# Lampen.net
KiCad netlist of a schematic drawn in EAGLE
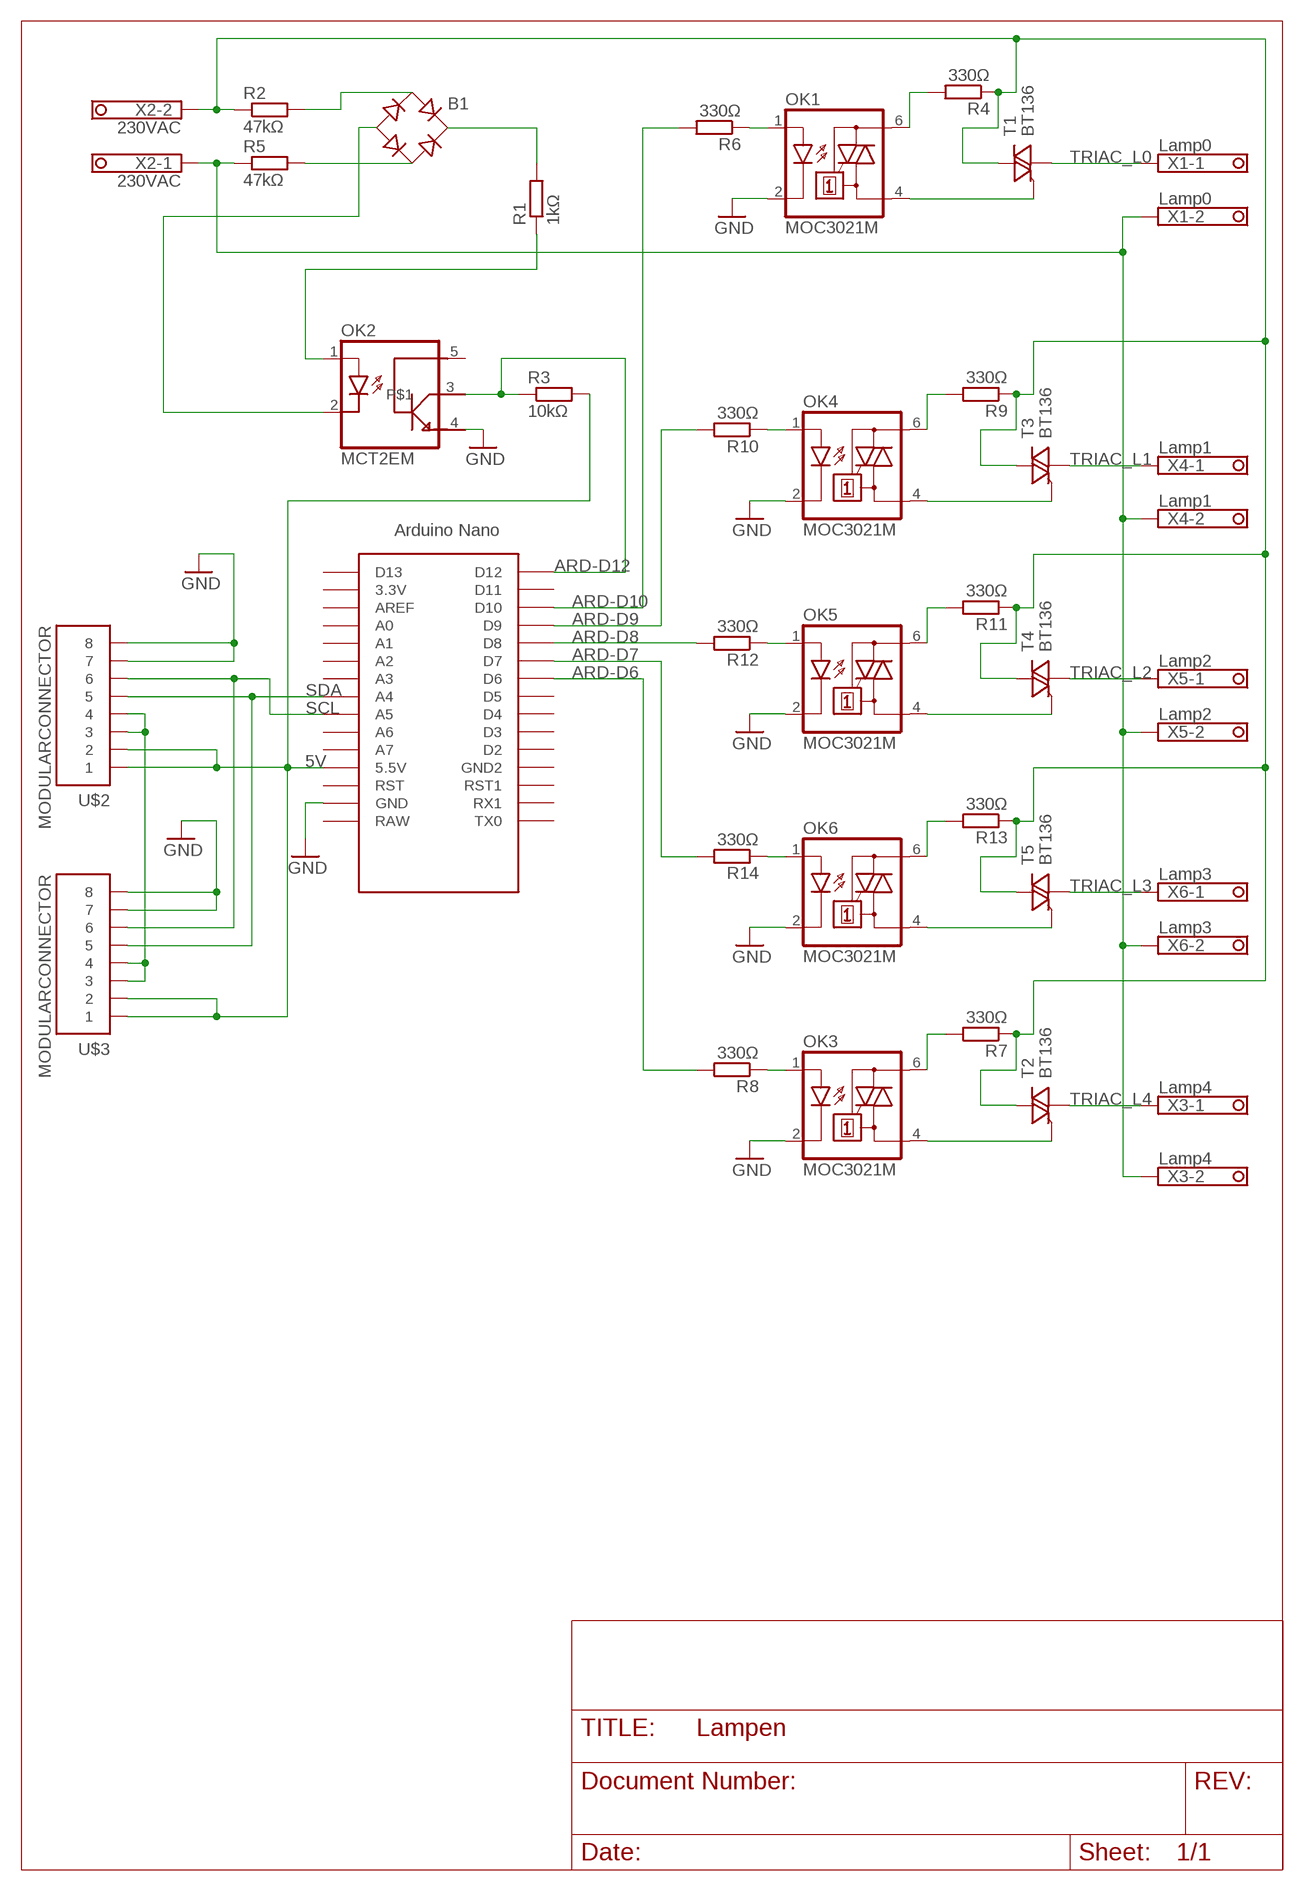
[diagram p0: schematic, sheet 1]

(export (version "E")
  (design (tool "Eeschema 10.0.6"))
  (components
    (comp (ref "B1")
      (value "B250C1500G")
      (footprint "eagle-import:RB1A")
      (libsource (lib "eagle-import") (part "B250C1500G"))
    )
    (comp (ref "OK1")
      (value "MOC3021M")
      (footprint "eagle-import:DIL06")
      (fields (field (name "MF") "FAIRCHILD SEMICONDUCTOR") (field (name "MPN") "MOC3010-M"))
      (libsource (lib "eagle-import") (part "MOC3021M10"))
    )
    (comp (ref "OK2")
      (value "MCT2EM")
      (footprint "eagle-import:DIL06")
      (fields (field (name "MF") "FAIRCHILD SEMICONDUCTOR") (field (name "MPN") "MOC3021-M"))
      (libsource (lib "eagle-import") (part "MCT2EM21"))
    )
    (comp (ref "OK3")
      (value "MOC3021M")
      (footprint "eagle-import:DIL06")
      (fields (field (name "MF") "FAIRCHILD SEMICONDUCTOR") (field (name "MPN") "MOC3010-M"))
      (libsource (lib "eagle-import") (part "MOC3021M10"))
    )
    (comp (ref "OK4")
      (value "MOC3021M")
      (footprint "eagle-import:DIL06")
      (fields (field (name "MF") "FAIRCHILD SEMICONDUCTOR") (field (name "MPN") "MOC3010-M"))
      (libsource (lib "eagle-import") (part "MOC3021M10"))
    )
    (comp (ref "OK5")
      (value "MOC3021M")
      (footprint "eagle-import:DIL06")
      (fields (field (name "MF") "FAIRCHILD SEMICONDUCTOR") (field (name "MPN") "MOC3010-M"))
      (libsource (lib "eagle-import") (part "MOC3021M10"))
    )
    (comp (ref "OK6")
      (value "MOC3021M")
      (footprint "eagle-import:DIL06")
      (fields (field (name "MF") "FAIRCHILD SEMICONDUCTOR") (field (name "MPN") "MOC3010-M"))
      (libsource (lib "eagle-import") (part "MOC3021M10"))
    )
    (comp (ref "R1")
      (value "1kΩ")
      (footprint "eagle-import:M1206")
      (libsource (lib "eagle-import") (part "R-EU_M1206"))
    )
    (comp (ref "R2")
      (value "47kΩ")
      (footprint "eagle-import:R2512")
      (libsource (lib "eagle-import") (part "R-EU_R2512"))
    )
    (comp (ref "R3")
      (value "10kΩ")
      (footprint "eagle-import:M1206")
      (libsource (lib "eagle-import") (part "R-EU_M1206"))
    )
    (comp (ref "R4")
      (value "330Ω")
      (footprint "eagle-import:M1206")
      (libsource (lib "eagle-import") (part "R-EU_M1206"))
    )
    (comp (ref "R5")
      (value "47kΩ")
      (footprint "eagle-import:R2512")
      (libsource (lib "eagle-import") (part "R-EU_R2512"))
    )
    (comp (ref "R6")
      (value "330Ω")
      (footprint "eagle-import:M1206")
      (libsource (lib "eagle-import") (part "R-EU_M1206"))
    )
    (comp (ref "R7")
      (value "330Ω")
      (footprint "eagle-import:M1206")
      (libsource (lib "eagle-import") (part "R-EU_M1206"))
    )
    (comp (ref "R8")
      (value "330Ω")
      (footprint "eagle-import:M1206")
      (libsource (lib "eagle-import") (part "R-EU_M1206"))
    )
    (comp (ref "R9")
      (value "330Ω")
      (footprint "eagle-import:M1206")
      (libsource (lib "eagle-import") (part "R-EU_M1206"))
    )
    (comp (ref "R10")
      (value "330Ω")
      (footprint "eagle-import:M1206")
      (libsource (lib "eagle-import") (part "R-EU_M1206"))
    )
    (comp (ref "R11")
      (value "330Ω")
      (footprint "eagle-import:M1206")
      (libsource (lib "eagle-import") (part "R-EU_M1206"))
    )
    (comp (ref "R12")
      (value "330Ω")
      (footprint "eagle-import:M1206")
      (libsource (lib "eagle-import") (part "R-EU_M1206"))
    )
    (comp (ref "R13")
      (value "330Ω")
      (footprint "eagle-import:M1206")
      (libsource (lib "eagle-import") (part "R-EU_M1206"))
    )
    (comp (ref "R14")
      (value "330Ω")
      (footprint "eagle-import:M1206")
      (libsource (lib "eagle-import") (part "R-EU_M1206"))
    )
    (comp (ref "T1")
      (value "BT136")
      (footprint "eagle-import:TO220DS")
      (libsource (lib "eagle-import") (part "BT136"))
    )
    (comp (ref "T2")
      (value "BT136")
      (footprint "eagle-import:TO220DS")
      (libsource (lib "eagle-import") (part "BT136"))
    )
    (comp (ref "T3")
      (value "BT136")
      (footprint "eagle-import:TO220DS")
      (libsource (lib "eagle-import") (part "BT136"))
    )
    (comp (ref "T4")
      (value "BT136")
      (footprint "eagle-import:TO220DS")
      (libsource (lib "eagle-import") (part "BT136"))
    )
    (comp (ref "T5")
      (value "BT136")
      (footprint "eagle-import:TO220DS")
      (libsource (lib "eagle-import") (part "BT136"))
    )
    (comp (ref "U$1")
      (value "NANO")
      (footprint "eagle-import:NANO")
      (libsource (lib "eagle-import") (part "NANO"))
    )
    (comp (ref "U$2")
      (value "MODULARCONNECTOR")
      (footprint "eagle-import:MA04-2")
      (libsource (lib "eagle-import") (part "MODULARCONNECTOR"))
    )
    (comp (ref "U$3")
      (value "MODULARCONNECTOR")
      (footprint "eagle-import:MA04-2")
      (libsource (lib "eagle-import") (part "MODULARCONNECTOR"))
    )
    (comp (ref "X1")
      (value "Lamp0")
      (footprint "eagle-import:1751248")
      (libsource (lib "eagle-import") (part "1751248"))
    )
    (comp (ref "X2")
      (value "230VAC")
      (footprint "eagle-import:1751248")
      (libsource (lib "eagle-import") (part "1751248"))
    )
    (comp (ref "X3")
      (value "Lamp4")
      (footprint "eagle-import:1751248")
      (libsource (lib "eagle-import") (part "1751248"))
    )
    (comp (ref "X4")
      (value "Lamp1")
      (footprint "eagle-import:1751248")
      (libsource (lib "eagle-import") (part "1751248"))
    )
    (comp (ref "X5")
      (value "Lamp2")
      (footprint "eagle-import:1751248")
      (libsource (lib "eagle-import") (part "1751248"))
    )
    (comp (ref "X6")
      (value "Lamp3")
      (footprint "eagle-import:1751248")
      (libsource (lib "eagle-import") (part "1751248"))
    )
  )
  (nets
    (net (code "1") (name "/5V") (class "Default")
      (node (ref "R3") (pin "2") (pinfunction "2_2") (pintype "passive"))
      (node (ref "U$1") (pin "5V") (pinfunction "5.5V_5V") (pintype "bidirectional"))
      (node (ref "U$2") (pin "1") (pinfunction "1_1") (pintype "input"))
      (node (ref "U$2") (pin "2") (pinfunction "2_2") (pintype "input"))
      (node (ref "U$3") (pin "1") (pinfunction "1_1") (pintype "input"))
      (node (ref "U$3") (pin "2") (pinfunction "2_2") (pintype "input"))
    )
    (net (code "2") (name "/ARD-D6") (class "Default")
      (node (ref "R8") (pin "2") (pinfunction "2_2") (pintype "passive"))
      (node (ref "U$1") (pin "D6") (pinfunction "D6_D6") (pintype "bidirectional"))
    )
    (net (code "3") (name "/ARD-D7") (class "Default")
      (node (ref "R14") (pin "2") (pinfunction "2_2") (pintype "passive"))
      (node (ref "U$1") (pin "D7") (pinfunction "D7_D7") (pintype "bidirectional"))
    )
    (net (code "4") (name "/ARD-D8") (class "Default")
      (node (ref "R12") (pin "2") (pinfunction "2_2") (pintype "passive"))
      (node (ref "U$1") (pin "D8") (pinfunction "D8_D8") (pintype "bidirectional"))
    )
    (net (code "5") (name "/ARD-D9") (class "Default")
      (node (ref "R10") (pin "2") (pinfunction "2_2") (pintype "passive"))
      (node (ref "U$1") (pin "D9") (pinfunction "D9_D9") (pintype "bidirectional"))
    )
    (net (code "6") (name "/ARD-D10") (class "Default")
      (node (ref "R6") (pin "2") (pinfunction "2_2") (pintype "passive"))
      (node (ref "U$1") (pin "D10") (pinfunction "D10_D10") (pintype "bidirectional"))
    )
    (net (code "7") (name "/ARD-D12") (class "Default")
      (node (ref "OK2") (pin "3") (pinfunction "P$1_3") (pintype "bidirectional"))
      (node (ref "R3") (pin "1") (pinfunction "1_1") (pintype "passive"))
      (node (ref "U$1") (pin "D12") (pinfunction "D12_D12") (pintype "bidirectional"))
    )
    (net (code "8") (name "/SCL") (class "Default")
      (node (ref "U$1") (pin "A5") (pinfunction "A5_A5") (pintype "bidirectional"))
      (node (ref "U$2") (pin "6") (pinfunction "6_6") (pintype "input"))
      (node (ref "U$3") (pin "6") (pinfunction "6_6") (pintype "input"))
    )
    (net (code "9") (name "/SDA") (class "Default")
      (node (ref "U$1") (pin "A4") (pinfunction "A4_A4") (pintype "bidirectional"))
      (node (ref "U$2") (pin "5") (pinfunction "5_5") (pintype "input"))
      (node (ref "U$3") (pin "5") (pinfunction "5_5") (pintype "input"))
    )
    (net (code "10") (name "/TRIAC_L0") (class "Default")
      (node (ref "T1") (pin "A1") (pinfunction "A1_A1") (pintype "passive"))
      (node (ref "X1") (pin "1") (pinfunction "K_1") (pintype "passive"))
    )
    (net (code "11") (name "/TRIAC_L1") (class "Default")
      (node (ref "T3") (pin "A1") (pinfunction "A1_A1") (pintype "passive"))
      (node (ref "X4") (pin "1") (pinfunction "K_1") (pintype "passive"))
    )
    (net (code "12") (name "/TRIAC_L2") (class "Default")
      (node (ref "T4") (pin "A1") (pinfunction "A1_A1") (pintype "passive"))
      (node (ref "X5") (pin "1") (pinfunction "K_1") (pintype "passive"))
    )
    (net (code "13") (name "/TRIAC_L3") (class "Default")
      (node (ref "T5") (pin "A1") (pinfunction "A1_A1") (pintype "passive"))
      (node (ref "X6") (pin "1") (pinfunction "K_1") (pintype "passive"))
    )
    (net (code "14") (name "/TRIAC_L4") (class "Default")
      (node (ref "T2") (pin "A1") (pinfunction "A1_A1") (pintype "passive"))
      (node (ref "X3") (pin "1") (pinfunction "K_1") (pintype "passive"))
    )
    (net (code "15") (name "GND") (class "Default")
      (node (ref "OK1") (pin "2") (pinfunction "C_2") (pintype "passive"))
      (node (ref "OK2") (pin "4") (pinfunction "A1_4") (pintype "passive"))
      (node (ref "OK3") (pin "2") (pinfunction "C_2") (pintype "passive"))
      (node (ref "OK4") (pin "2") (pinfunction "C_2") (pintype "passive"))
      (node (ref "OK5") (pin "2") (pinfunction "C_2") (pintype "passive"))
      (node (ref "OK6") (pin "2") (pinfunction "C_2") (pintype "passive"))
      (node (ref "U$1") (pin "GND") (pinfunction "GND_GND") (pintype "bidirectional"))
      (node (ref "U$2") (pin "7") (pinfunction "7_7") (pintype "input"))
      (node (ref "U$2") (pin "8") (pinfunction "8_8") (pintype "input"))
      (node (ref "U$3") (pin "7") (pinfunction "7_7") (pintype "input"))
      (node (ref "U$3") (pin "8") (pinfunction "8_8") (pintype "input"))
    )
    (net (code "16") (name "Net-(B1-Pad+)") (class "Default")
      (node (ref "B1") (pin "+") (pinfunction "+_+") (pintype "passive"))
      (node (ref "R1") (pin "2") (pinfunction "2_2") (pintype "passive"))
    )
    (net (code "17") (name "Net-(B1-PadAC1)") (class "Default")
      (node (ref "B1") (pin "AC1") (pinfunction "AC1_AC1") (pintype "passive"))
      (node (ref "R2") (pin "2") (pinfunction "2_2") (pintype "passive"))
    )
    (net (code "18") (name "Net-(B1-PadAC2)") (class "Default")
      (node (ref "B1") (pin "AC2") (pinfunction "AC2_AC2") (pintype "passive"))
      (node (ref "R5") (pin "2") (pinfunction "2_2") (pintype "passive"))
    )
    (net (code "19") (name "Net-(OK1-A)") (class "Default")
      (node (ref "OK1") (pin "1") (pinfunction "A_1") (pintype "passive"))
      (node (ref "R6") (pin "1") (pinfunction "1_1") (pintype "passive"))
    )
    (net (code "20") (name "Net-(OK1-A1)") (class "Default")
      (node (ref "OK1") (pin "4") (pinfunction "A1_4") (pintype "passive"))
      (node (ref "T1") (pin "G") (pinfunction "G_G") (pintype "passive"))
    )
    (net (code "21") (name "Net-(OK1-A2)") (class "Default")
      (node (ref "OK1") (pin "6") (pinfunction "A2_6") (pintype "passive"))
      (node (ref "R4") (pin "2") (pinfunction "2_2") (pintype "passive"))
    )
    (net (code "22") (name "Net-(OK2-A)") (class "Default")
      (node (ref "OK2") (pin "1") (pinfunction "A_1") (pintype "passive"))
      (node (ref "R1") (pin "1") (pinfunction "1_1") (pintype "passive"))
    )
    (net (code "23") (name "Net-(OK2-C)") (class "Default")
      (node (ref "B1") (pin "-") (pinfunction "-_-") (pintype "passive"))
      (node (ref "OK2") (pin "2") (pinfunction "C_2") (pintype "passive"))
    )
    (net (code "24") (name "Net-(OK3-A)") (class "Default")
      (node (ref "OK3") (pin "1") (pinfunction "A_1") (pintype "passive"))
      (node (ref "R8") (pin "1") (pinfunction "1_1") (pintype "passive"))
    )
    (net (code "25") (name "Net-(OK3-A1)") (class "Default")
      (node (ref "OK3") (pin "4") (pinfunction "A1_4") (pintype "passive"))
      (node (ref "T2") (pin "G") (pinfunction "G_G") (pintype "passive"))
    )
    (net (code "26") (name "Net-(OK3-A2)") (class "Default")
      (node (ref "OK3") (pin "6") (pinfunction "A2_6") (pintype "passive"))
      (node (ref "R7") (pin "2") (pinfunction "2_2") (pintype "passive"))
    )
    (net (code "27") (name "Net-(OK4-A)") (class "Default")
      (node (ref "OK4") (pin "1") (pinfunction "A_1") (pintype "passive"))
      (node (ref "R10") (pin "1") (pinfunction "1_1") (pintype "passive"))
    )
    (net (code "28") (name "Net-(OK4-A1)") (class "Default")
      (node (ref "OK4") (pin "4") (pinfunction "A1_4") (pintype "passive"))
      (node (ref "T3") (pin "G") (pinfunction "G_G") (pintype "passive"))
    )
    (net (code "29") (name "Net-(OK4-A2)") (class "Default")
      (node (ref "OK4") (pin "6") (pinfunction "A2_6") (pintype "passive"))
      (node (ref "R9") (pin "2") (pinfunction "2_2") (pintype "passive"))
    )
    (net (code "30") (name "Net-(OK5-A)") (class "Default")
      (node (ref "OK5") (pin "1") (pinfunction "A_1") (pintype "passive"))
      (node (ref "R12") (pin "1") (pinfunction "1_1") (pintype "passive"))
    )
    (net (code "31") (name "Net-(OK5-A1)") (class "Default")
      (node (ref "OK5") (pin "4") (pinfunction "A1_4") (pintype "passive"))
      (node (ref "T4") (pin "G") (pinfunction "G_G") (pintype "passive"))
    )
    (net (code "32") (name "Net-(OK5-A2)") (class "Default")
      (node (ref "OK5") (pin "6") (pinfunction "A2_6") (pintype "passive"))
      (node (ref "R11") (pin "2") (pinfunction "2_2") (pintype "passive"))
    )
    (net (code "33") (name "Net-(OK6-A)") (class "Default")
      (node (ref "OK6") (pin "1") (pinfunction "A_1") (pintype "passive"))
      (node (ref "R14") (pin "1") (pinfunction "1_1") (pintype "passive"))
    )
    (net (code "34") (name "Net-(OK6-A1)") (class "Default")
      (node (ref "OK6") (pin "4") (pinfunction "A1_4") (pintype "passive"))
      (node (ref "T5") (pin "G") (pinfunction "G_G") (pintype "passive"))
    )
    (net (code "35") (name "Net-(OK6-A2)") (class "Default")
      (node (ref "OK6") (pin "6") (pinfunction "A2_6") (pintype "passive"))
      (node (ref "R13") (pin "2") (pinfunction "2_2") (pintype "passive"))
    )
    (net (code "36") (name "Net-(U$2-Pad3)") (class "Default")
      (node (ref "U$2") (pin "3") (pinfunction "3_3") (pintype "input"))
      (node (ref "U$2") (pin "4") (pinfunction "4_4") (pintype "input"))
      (node (ref "U$3") (pin "3") (pinfunction "3_3") (pintype "input"))
      (node (ref "U$3") (pin "4") (pinfunction "4_4") (pintype "input"))
    )
    (net (code "37") (name "Net-(X1B-K)") (class "Default")
      (node (ref "R5") (pin "1") (pinfunction "1_1") (pintype "passive"))
      (node (ref "X1") (pin "2") (pinfunction "K_2") (pintype "passive"))
      (node (ref "X2") (pin "1") (pinfunction "K_1") (pintype "passive"))
      (node (ref "X3") (pin "2") (pinfunction "K_2") (pintype "passive"))
      (node (ref "X4") (pin "2") (pinfunction "K_2") (pintype "passive"))
      (node (ref "X5") (pin "2") (pinfunction "K_2") (pintype "passive"))
      (node (ref "X6") (pin "2") (pinfunction "K_2") (pintype "passive"))
    )
    (net (code "38") (name "Net-(X2B-K)") (class "Default")
      (node (ref "R11") (pin "1") (pinfunction "1_1") (pintype "passive"))
      (node (ref "R13") (pin "1") (pinfunction "1_1") (pintype "passive"))
      (node (ref "R2") (pin "1") (pinfunction "1_1") (pintype "passive"))
      (node (ref "R4") (pin "1") (pinfunction "1_1") (pintype "passive"))
      (node (ref "R7") (pin "1") (pinfunction "1_1") (pintype "passive"))
      (node (ref "R9") (pin "1") (pinfunction "1_1") (pintype "passive"))
      (node (ref "T1") (pin "A2") (pinfunction "A2_A2") (pintype "passive"))
      (node (ref "T2") (pin "A2") (pinfunction "A2_A2") (pintype "passive"))
      (node (ref "T3") (pin "A2") (pinfunction "A2_A2") (pintype "passive"))
      (node (ref "T4") (pin "A2") (pinfunction "A2_A2") (pintype "passive"))
      (node (ref "T5") (pin "A2") (pinfunction "A2_A2") (pintype "passive"))
      (node (ref "X2") (pin "2") (pinfunction "K_2") (pintype "passive"))
    )
    (net (code "39") (name "unconnected-(OK2-A2-Pad5)") (class "Default")
      (node (ref "OK2") (pin "5") (pinfunction "A2_5") (pintype "passive"))
    )
    (net (code "40") (name "unconnected-(U$1-GND2-PadGND1)") (class "Default")
      (node (ref "U$1") (pin "GND1") (pinfunction "GND2_GND1") (pintype "bidirectional"))
    )
    (net (code "41") (name "unconnected-(U$1-Pad3.3V)") (class "Default")
      (node (ref "U$1") (pin "3.3V") (pinfunction "3.3V_3.3V") (pintype "bidirectional"))
    )
    (net (code "42") (name "unconnected-(U$1-PadA0)") (class "Default")
      (node (ref "U$1") (pin "A0") (pinfunction "A0_A0") (pintype "bidirectional"))
    )
    (net (code "43") (name "unconnected-(U$1-PadA1)") (class "Default")
      (node (ref "U$1") (pin "A1") (pinfunction "A1_A1") (pintype "bidirectional"))
    )
    (net (code "44") (name "unconnected-(U$1-PadA2)") (class "Default")
      (node (ref "U$1") (pin "A2") (pinfunction "A2_A2") (pintype "bidirectional"))
    )
    (net (code "45") (name "unconnected-(U$1-PadA3)") (class "Default")
      (node (ref "U$1") (pin "A3") (pinfunction "A3_A3") (pintype "bidirectional"))
    )
    (net (code "46") (name "unconnected-(U$1-PadA6)") (class "Default")
      (node (ref "U$1") (pin "A6") (pinfunction "A6_A6") (pintype "bidirectional"))
    )
    (net (code "47") (name "unconnected-(U$1-PadA7)") (class "Default")
      (node (ref "U$1") (pin "A7") (pinfunction "A7_A7") (pintype "bidirectional"))
    )
    (net (code "48") (name "unconnected-(U$1-PadAREF)") (class "Default")
      (node (ref "U$1") (pin "AREF") (pinfunction "AREF_AREF") (pintype "bidirectional"))
    )
    (net (code "49") (name "unconnected-(U$1-PadD2)") (class "Default")
      (node (ref "U$1") (pin "D2") (pinfunction "D2_D2") (pintype "bidirectional"))
    )
    (net (code "50") (name "unconnected-(U$1-PadD3)") (class "Default")
      (node (ref "U$1") (pin "D3") (pinfunction "D3_D3") (pintype "bidirectional"))
    )
    (net (code "51") (name "unconnected-(U$1-PadD4)") (class "Default")
      (node (ref "U$1") (pin "D4") (pinfunction "D4_D4") (pintype "bidirectional"))
    )
    (net (code "52") (name "unconnected-(U$1-PadD5)") (class "Default")
      (node (ref "U$1") (pin "D5") (pinfunction "D5_D5") (pintype "bidirectional"))
    )
    (net (code "53") (name "unconnected-(U$1-PadD11)") (class "Default")
      (node (ref "U$1") (pin "D11") (pinfunction "D11_D11") (pintype "bidirectional"))
    )
    (net (code "54") (name "unconnected-(U$1-PadD13)") (class "Default")
      (node (ref "U$1") (pin "D13") (pinfunction "D13_D13") (pintype "bidirectional"))
    )
    (net (code "55") (name "unconnected-(U$1-PadICSP1)") (class "Default")
      (node (ref "U$1") (pin "ICSP1") (pinfunction "ICSP1_ICSP1") (pintype "bidirectional"))
    )
    (net (code "56") (name "unconnected-(U$1-PadICSP2)") (class "Default")
      (node (ref "U$1") (pin "ICSP2") (pinfunction "ICSP2_ICSP2") (pintype "bidirectional"))
    )
    (net (code "57") (name "unconnected-(U$1-PadICSP3)") (class "Default")
      (node (ref "U$1") (pin "ICSP3") (pinfunction "ICSP3_ICSP3") (pintype "bidirectional"))
    )
    (net (code "58") (name "unconnected-(U$1-PadICSP4)") (class "Default")
      (node (ref "U$1") (pin "ICSP4") (pinfunction "ICSP4_ICSP4") (pintype "bidirectional"))
    )
    (net (code "59") (name "unconnected-(U$1-PadICSP5)") (class "Default")
      (node (ref "U$1") (pin "ICSP5") (pinfunction "ICSP5_ICSP5") (pintype "bidirectional"))
    )
    (net (code "60") (name "unconnected-(U$1-PadICSP6)") (class "Default")
      (node (ref "U$1") (pin "ICSP6") (pinfunction "ICSP6_ICSP6") (pintype "bidirectional"))
    )
    (net (code "61") (name "unconnected-(U$1-PadRAW)") (class "Default")
      (node (ref "U$1") (pin "RAW") (pinfunction "RAW_RAW") (pintype "bidirectional"))
    )
    (net (code "62") (name "unconnected-(U$1-PadRST)") (class "Default")
      (node (ref "U$1") (pin "RST") (pinfunction "RST_RST") (pintype "bidirectional"))
    )
    (net (code "63") (name "unconnected-(U$1-PadRST1)") (class "Default")
      (node (ref "U$1") (pin "RST1") (pinfunction "RST1_RST1") (pintype "bidirectional"))
    )
    (net (code "64") (name "unconnected-(U$1-PadRX1)") (class "Default")
      (node (ref "U$1") (pin "RX1") (pinfunction "RX1_RX1") (pintype "bidirectional"))
    )
    (net (code "65") (name "unconnected-(U$1-PadTX0)") (class "Default")
      (node (ref "U$1") (pin "TX0") (pinfunction "TX0_TX0") (pintype "bidirectional"))
    )
  )
)
